# NMOS_motor_SW.net
KiCad netlist of a schematic drawn in Altium Designer
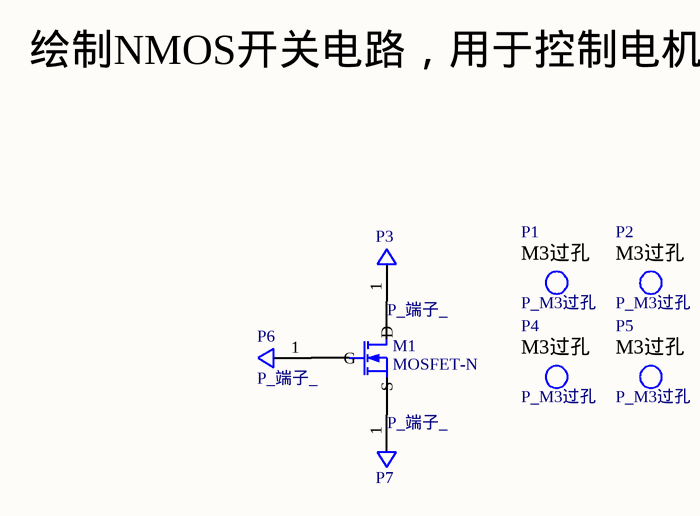
[diagram p0: NMOS_motor_SW.SchDoc]

(export (version "E")
  (design (tool "Eeschema 10.0.6"))
  (components
    (comp (ref "M1")
      (value "MOSFET-N")
      (footprint "MOSFET_N-CHANNEL_IRLR8726PBF")
      (description "N-Channel MOSFET")
      (fields (field (name "PUBLISHER") "Altium Limited"))
      (libsource (lib "Titan_Schlib1") (part "MOSFET-N"))
    )
    (comp (ref "P1") (value "P_M3过孔") (footprint "P_M3过孔") (libsource (lib "Titan_Schlib1") (part "P_M3过孔")))
    (comp (ref "P2") (value "P_M3过孔") (footprint "P_M3过孔") (libsource (lib "Titan_Schlib1") (part "P_M3过孔")))
    (comp (ref "P3") (value "P_端子_") (footprint "P_排母_2*1") (libsource (lib "Titan_Schlib1") (part "P_端子_")))
    (comp (ref "P4") (value "P_M3过孔") (footprint "P_M3过孔") (libsource (lib "Titan_Schlib1") (part "P_M3过孔")))
    (comp (ref "P5") (value "P_M3过孔") (footprint "P_M3过孔") (libsource (lib "Titan_Schlib1") (part "P_M3过孔")))
    (comp (ref "P6") (value "P_端子_") (footprint "P_排母_2*1") (libsource (lib "Titan_Schlib1") (part "P_端子_")))
    (comp (ref "P7") (value "P_端子_") (footprint "P_排母_2*1") (libsource (lib "Titan_Schlib1") (part "P_端子_")))
  )
  (nets
    (net (code "1") (name "Net-(M1-D)") (class "Default")
      (node (ref "M1") (pin "2") (pinfunction "D_2") (pintype "passive"))
      (node (ref "P3") (pin "1") (pinfunction "pin1_1") (pintype "passive"))
    )
    (net (code "2") (name "Net-(M1-G)") (class "Default")
      (node (ref "M1") (pin "1") (pinfunction "G_1") (pintype "passive"))
      (node (ref "P6") (pin "1") (pinfunction "pin1_1") (pintype "passive"))
    )
    (net (code "3") (name "Net-(M1-S)") (class "Default")
      (node (ref "M1") (pin "3") (pinfunction "S_3") (pintype "passive"))
      (node (ref "P7") (pin "1") (pinfunction "pin1_1") (pintype "passive"))
    )
  )
)
